# BlinkyBoard.net
KiCad netlist of a schematic drawn in EAGLE
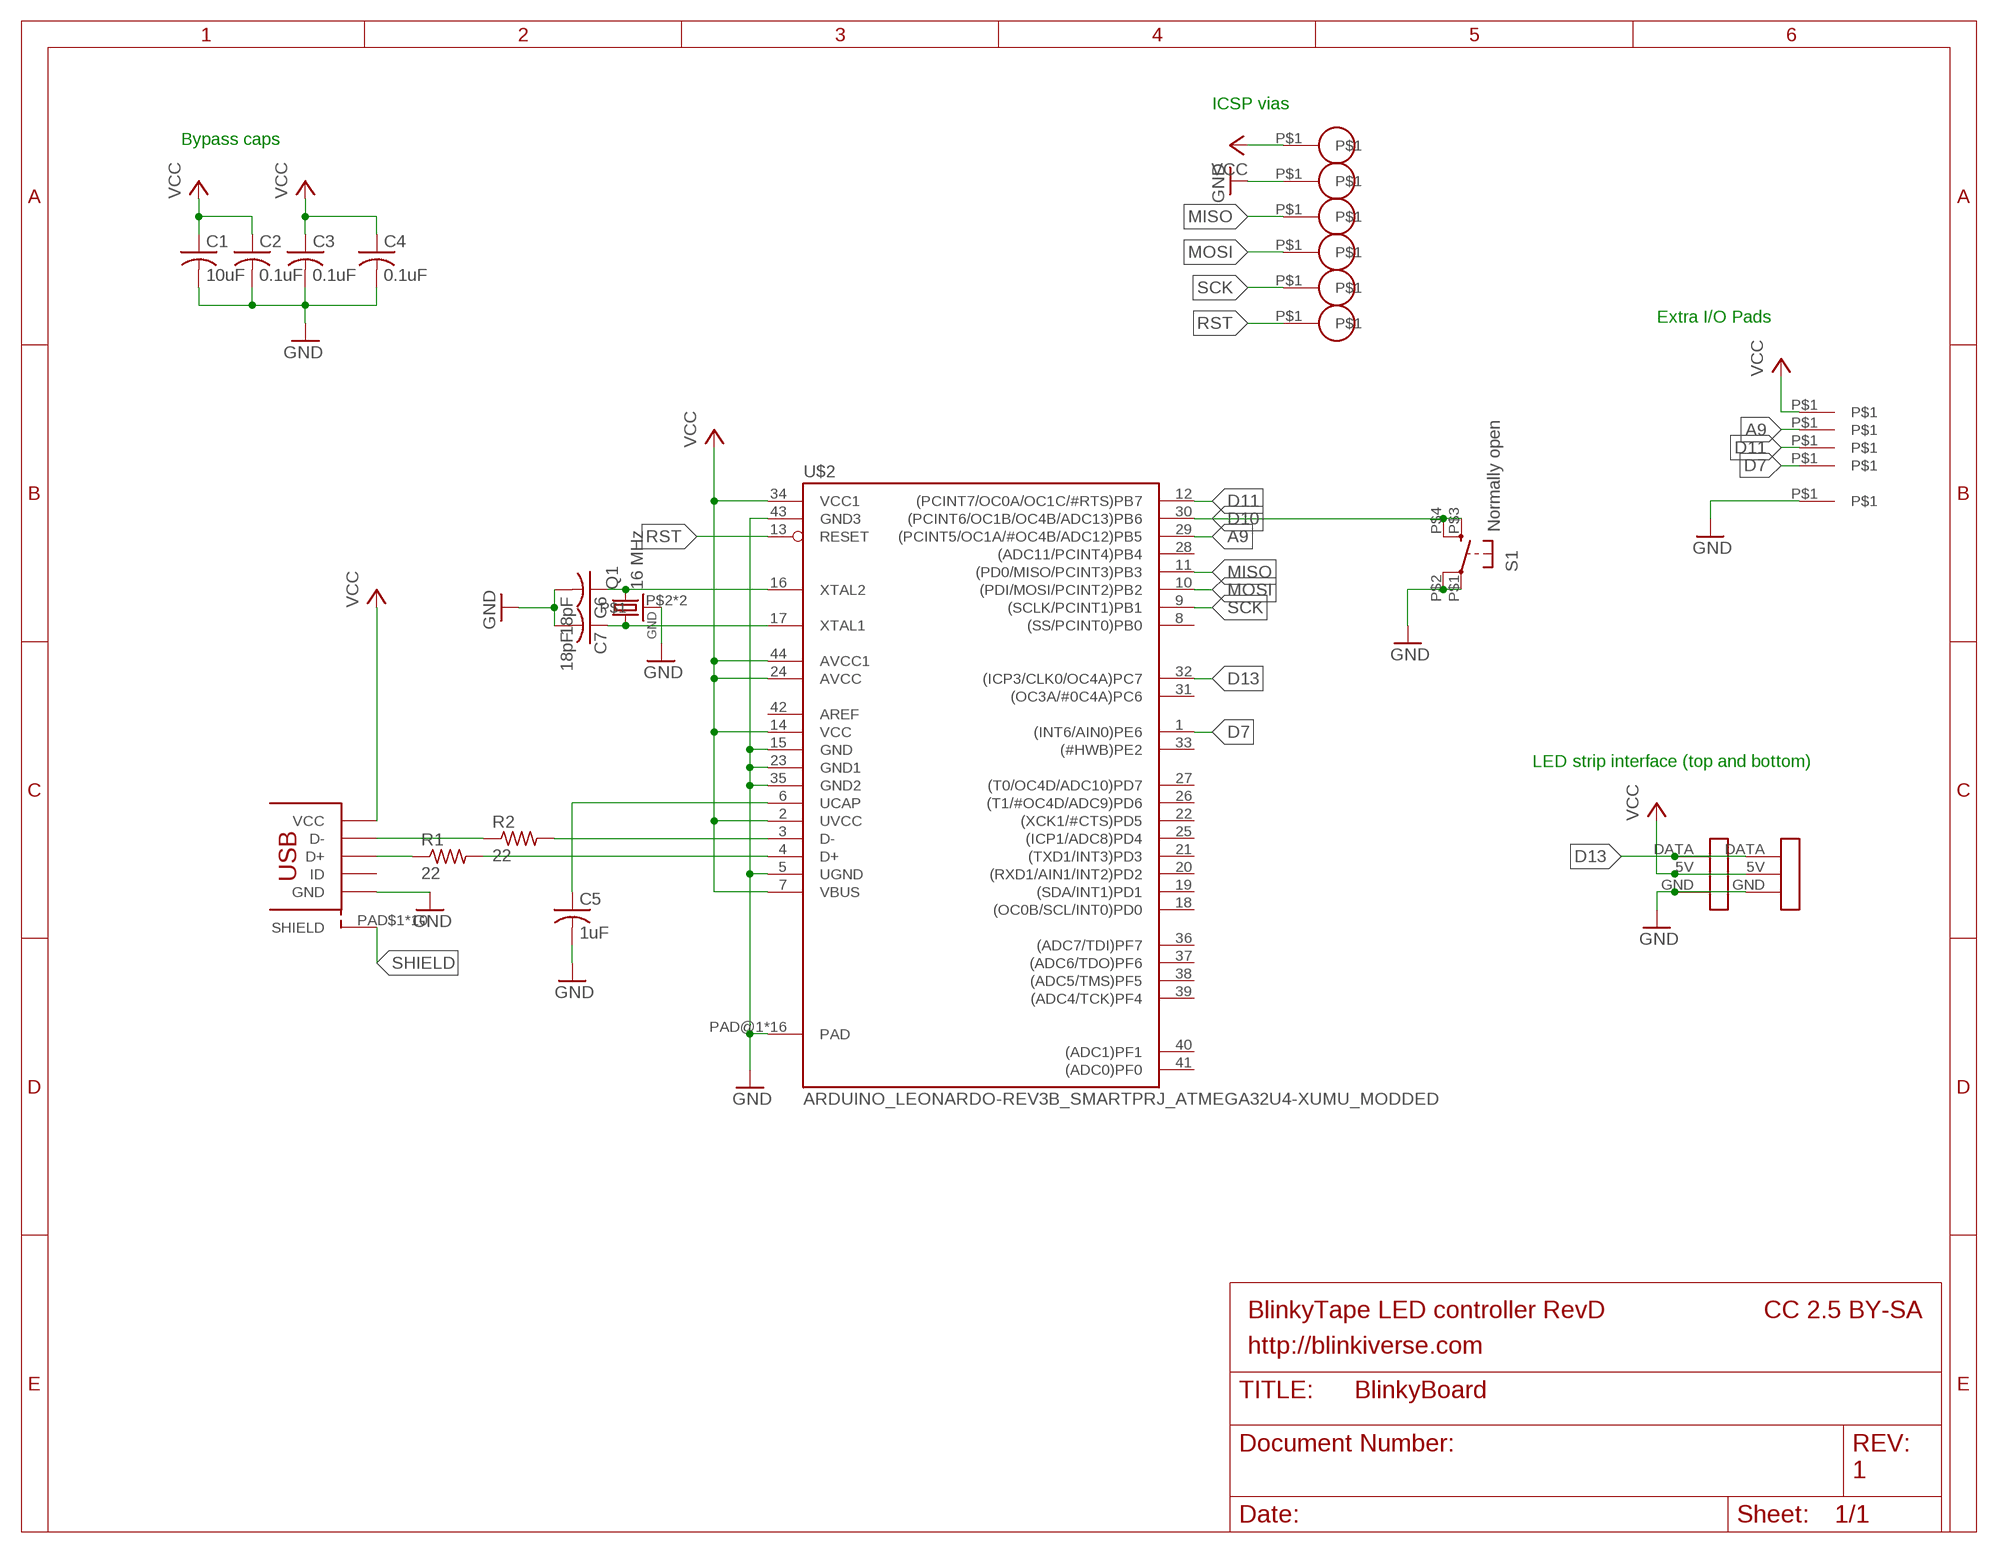
[diagram p0: schematic, sheet 1]

(export (version "E")
  (design (tool "Eeschema 10.0.6"))
  (components
    (comp (ref "C1")
      (value "10uF")
      (footprint "eagle-import:C0603K")
      (libsource (lib "eagle-import") (part "C-USC0603K"))
    )
    (comp (ref "C2")
      (value "0.1uF")
      (footprint "eagle-import:CAP_0402_KEMET_MEDIAN")
      (libsource (lib "eagle-import") (part "C_US"))
    )
    (comp (ref "C3")
      (value "0.1uF")
      (footprint "eagle-import:CAP_0402_KEMET_MEDIAN")
      (libsource (lib "eagle-import") (part "C_US"))
    )
    (comp (ref "C4")
      (value "0.1uF")
      (footprint "eagle-import:CAP_0402_KEMET_MEDIAN")
      (libsource (lib "eagle-import") (part "C_US"))
    )
    (comp (ref "C5")
      (value "1uF")
      (footprint "eagle-import:CAP_0402_KEMET_MEDIAN")
      (libsource (lib "eagle-import") (part "C_US"))
    )
    (comp (ref "C6")
      (value "18pF")
      (footprint "eagle-import:CAP_0402_KEMET_MEDIAN")
      (libsource (lib "eagle-import") (part "C_US"))
    )
    (comp (ref "C7")
      (value "18pF")
      (footprint "eagle-import:CAP_0402_KEMET_MEDIAN")
      (libsource (lib "eagle-import") (part "C_US"))
    )
    (comp (ref "Q1")
      (value "16 MHz")
      (footprint "eagle-import:CRSYTAL_2520")
      (libsource (lib "eagle-import") (part "CRYSTAL_4PAD2520"))
    )
    (comp (ref "R1")
      (value "22")
      (footprint "eagle-import:RES_0402_KEMET_MEDIAN")
      (libsource (lib "eagle-import") (part "R_US"))
    )
    (comp (ref "R2")
      (value "22")
      (footprint "eagle-import:RES_0402_KEMET_MEDIAN")
      (libsource (lib "eagle-import") (part "R_US"))
    )
    (comp (ref "S1")
      (value "Normally open")
      (footprint "eagle-import:GLOWBOARD_KMR211G_SWITCH")
      (libsource (lib "eagle-import") (part "GLOWBOARD_KMR211G"))
    )
    (comp (ref "U$1")
      (value "TEST_VIA")
      (footprint "eagle-import:TEST_VIA_.5MM")
      (libsource (lib "eagle-import") (part "TEST_VIA"))
    )
    (comp (ref "U$2")
      (value "ARDUINO_LEONARDO-REV3B_SMARTPRJ_ATMEGA32U4-XUMU_MODDED")
      (footprint "eagle-import:QFN44ML_7X7_LONGLEADS_MOD")
      (libsource (lib "eagle-import") (part "ARDUINO_LEONARDO-REV3B_SMARTPRJ_ATMEGA32U4-XUMU_MODDED"))
    )
    (comp (ref "U$3")
      (value "TEST_VIA")
      (footprint "eagle-import:TEST_VIA_.5MM")
      (libsource (lib "eagle-import") (part "TEST_VIA"))
    )
    (comp (ref "U$4")
      (value "MICRO_USBSMT+THRUHULE")
      (footprint "eagle-import:MICRO_USB_FCI_THRUHOLE")
      (libsource (lib "eagle-import") (part "MICRO_USBSMT+THRUHULE"))
    )
    (comp (ref "U$5")
      (value "TEST_VIA")
      (footprint "eagle-import:TEST_VIA_.5MM")
      (libsource (lib "eagle-import") (part "TEST_VIA"))
    )
    (comp (ref "U$6")
      (value "TEST_VIA")
      (footprint "eagle-import:TEST_VIA_.5MM")
      (libsource (lib "eagle-import") (part "TEST_VIA"))
    )
    (comp (ref "U$7")
      (value "TEST_VIA")
      (footprint "eagle-import:TEST_VIA_.5MM")
      (libsource (lib "eagle-import") (part "TEST_VIA"))
    )
    (comp (ref "U$8")
      (value "TEST_VIA")
      (footprint "eagle-import:TEST_VIA_.5MM")
      (libsource (lib "eagle-import") (part "TEST_VIA"))
    )
    (comp (ref "U$10")
      (value "TEST_PAD_SMT")
      (footprint "eagle-import:TEST_PAD_SMT")
      (libsource (lib "eagle-import") (part "TEST_PAD_SMT"))
    )
    (comp (ref "U$11")
      (value "TEST_PAD_SMT")
      (footprint "eagle-import:TEST_PAD_SMT")
      (libsource (lib "eagle-import") (part "TEST_PAD_SMT"))
    )
    (comp (ref "U$12")
      (value "TEST_PAD_SMT")
      (footprint "eagle-import:TEST_PAD_SMT")
      (libsource (lib "eagle-import") (part "TEST_PAD_SMT"))
    )
    (comp (ref "U$13")
      (value "TEST_PAD_SMT")
      (footprint "eagle-import:TEST_PAD_SMT")
      (libsource (lib "eagle-import") (part "TEST_PAD_SMT"))
    )
    (comp (ref "U$14")
      (value "TEST_PAD_SMT")
      (footprint "eagle-import:TEST_PAD_SMT")
      (libsource (lib "eagle-import") (part "TEST_PAD_SMT"))
    )
    (comp (ref "WS1")
      (value "WS2811_CONNECTORSTRIP")
      (footprint "eagle-import:WS2811_CONNECTOR")
      (libsource (lib "eagle-import") (part "WS2811_CONNECTORSTRIP"))
    )
    (comp (ref "WS3")
      (value "WS2811_CONNECTORSTRIP")
      (footprint "eagle-import:WS2811_CONNECTOR")
      (libsource (lib "eagle-import") (part "WS2811_CONNECTORSTRIP"))
    )
  )
  (nets
    (net (code "1") (name "/AREF") (class "Default")
      (node (ref "U$2") (pin "42") (pinfunction "AREF_42") (pintype "power_in"))
    )
    (net (code "2") (name "A9") (class "Default")
      (node (ref "U$11") (pin "P$1") (pinfunction "P$1_P$1") (pintype "bidirectional"))
      (node (ref "U$2") (pin "29") (pinfunction "(PCINT5/OC1A/#OC4B/ADC12)PB5_29") (pintype "bidirectional"))
    )
    (net (code "3") (name "D7") (class "Default")
      (node (ref "U$10") (pin "P$1") (pinfunction "P$1_P$1") (pintype "bidirectional"))
      (node (ref "U$2") (pin "1") (pinfunction "(INT6/AIN0)PE6_1") (pintype "bidirectional"))
    )
    (net (code "4") (name "D10") (class "Default")
      (node (ref "S1") (pin "P$3") (pinfunction "S_P$3") (pintype "passive"))
      (node (ref "S1") (pin "P$4") (pinfunction "S1_P$4") (pintype "passive"))
      (node (ref "U$2") (pin "30") (pinfunction "(PCINT6/OC1B/OC4B/ADC13)PB6_30") (pintype "bidirectional"))
    )
    (net (code "5") (name "D11") (class "Default")
      (node (ref "U$14") (pin "P$1") (pinfunction "P$1_P$1") (pintype "bidirectional"))
      (node (ref "U$2") (pin "12") (pinfunction "(PCINT7/OC0A/OC1C/#RTS)PB7_12") (pintype "bidirectional"))
    )
    (net (code "6") (name "D13") (class "Default")
      (node (ref "U$2") (pin "32") (pinfunction "(ICP3/CLK0/OC4A)PC7_32") (pintype "bidirectional"))
      (node (ref "WS1") (pin "DATA") (pinfunction "DATA_DATA") (pintype "bidirectional"))
      (node (ref "WS3") (pin "DATA") (pinfunction "DATA_DATA") (pintype "bidirectional"))
    )
    (net (code "7") (name "GND") (class "Default")
      (node (ref "C1") (pin "2") (pinfunction "2_2") (pintype "passive"))
      (node (ref "C2") (pin "P$2") (pinfunction "2_P$2") (pintype "passive"))
      (node (ref "C3") (pin "P$2") (pinfunction "2_P$2") (pintype "passive"))
      (node (ref "C4") (pin "P$2") (pinfunction "2_P$2") (pintype "passive"))
      (node (ref "C5") (pin "P$2") (pinfunction "2_P$2") (pintype "passive"))
      (node (ref "C6") (pin "P$2") (pinfunction "2_P$2") (pintype "passive"))
      (node (ref "C7") (pin "P$2") (pinfunction "2_P$2") (pintype "passive"))
      (node (ref "Q1") (pin "P$2") (pinfunction "P$1_P$2") (pintype "bidirectional"))
      (node (ref "Q1") (pin "P$4") (pinfunction "P$1_P$4") (pintype "bidirectional"))
      (node (ref "S1") (pin "P$1") (pinfunction "P_P$1") (pintype "passive"))
      (node (ref "S1") (pin "P$2") (pinfunction "P1_P$2") (pintype "passive"))
      (node (ref "U$13") (pin "P$1") (pinfunction "P$1_P$1") (pintype "bidirectional"))
      (node (ref "U$2") (pin "15") (pinfunction "GND_15") (pintype "power_in"))
      (node (ref "U$2") (pin "23") (pinfunction "GND1_23") (pintype "power_in"))
      (node (ref "U$2") (pin "35") (pinfunction "GND2_35") (pintype "power_in"))
      (node (ref "U$2") (pin "43") (pinfunction "GND3_43") (pintype "power_in"))
      (node (ref "U$2") (pin "5") (pinfunction "UGND_5") (pintype "power_in"))
      (node (ref "U$2") (pin "PAD@1") (pinfunction "PAD_PAD@1") (pintype "power_in"))
      (node (ref "U$2") (pin "PAD@10") (pinfunction "PAD_PAD@10") (pintype "power_in"))
      (node (ref "U$2") (pin "PAD@11") (pinfunction "PAD_PAD@11") (pintype "power_in"))
      (node (ref "U$2") (pin "PAD@12") (pinfunction "PAD_PAD@12") (pintype "power_in"))
      (node (ref "U$2") (pin "PAD@13") (pinfunction "PAD_PAD@13") (pintype "power_in"))
      (node (ref "U$2") (pin "PAD@14") (pinfunction "PAD_PAD@14") (pintype "power_in"))
      (node (ref "U$2") (pin "PAD@15") (pinfunction "PAD_PAD@15") (pintype "power_in"))
      (node (ref "U$2") (pin "PAD@16") (pinfunction "PAD_PAD@16") (pintype "power_in"))
      (node (ref "U$2") (pin "PAD@2") (pinfunction "PAD_PAD@2") (pintype "power_in"))
      (node (ref "U$2") (pin "PAD@3") (pinfunction "PAD_PAD@3") (pintype "power_in"))
      (node (ref "U$2") (pin "PAD@4") (pinfunction "PAD_PAD@4") (pintype "power_in"))
      (node (ref "U$2") (pin "PAD@5") (pinfunction "PAD_PAD@5") (pintype "power_in"))
      (node (ref "U$2") (pin "PAD@6") (pinfunction "PAD_PAD@6") (pintype "power_in"))
      (node (ref "U$2") (pin "PAD@7") (pinfunction "PAD_PAD@7") (pintype "power_in"))
      (node (ref "U$2") (pin "PAD@8") (pinfunction "PAD_PAD@8") (pintype "power_in"))
      (node (ref "U$2") (pin "PAD@9") (pinfunction "PAD_PAD@9") (pintype "power_in"))
      (node (ref "U$4") (pin "PIN$5") (pinfunction "GND_PIN$5") (pintype "bidirectional"))
      (node (ref "U$7") (pin "P$1") (pinfunction "P$1_P$1") (pintype "bidirectional"))
      (node (ref "WS1") (pin "GND") (pinfunction "GND_GND") (pintype "bidirectional"))
      (node (ref "WS3") (pin "GND") (pinfunction "GND_GND") (pintype "bidirectional"))
    )
    (net (code "8") (name "MISO") (class "Default")
      (node (ref "U$1") (pin "P$1") (pinfunction "P$1_P$1") (pintype "bidirectional"))
      (node (ref "U$2") (pin "11") (pinfunction "(PD0/MISO/PCINT3)PB3_11") (pintype "bidirectional"))
    )
    (net (code "9") (name "MOSI") (class "Default")
      (node (ref "U$2") (pin "10") (pinfunction "(PDI/MOSI/PCINT2)PB2_10") (pintype "bidirectional"))
      (node (ref "U$3") (pin "P$1") (pinfunction "P$1_P$1") (pintype "bidirectional"))
    )
    (net (code "10") (name "Net-(C5-1)") (class "Default")
      (node (ref "C5") (pin "P$1") (pinfunction "1_P$1") (pintype "passive"))
      (node (ref "U$2") (pin "6") (pinfunction "UCAP_6") (pintype "passive"))
    )
    (net (code "11") (name "Net-(C6-1)") (class "Default")
      (node (ref "C6") (pin "P$1") (pinfunction "1_P$1") (pintype "passive"))
      (node (ref "Q1") (pin "P$3") (pinfunction "2_P$3") (pintype "passive"))
      (node (ref "U$2") (pin "16") (pinfunction "XTAL2_16") (pintype "bidirectional"))
    )
    (net (code "12") (name "Net-(C7-1)") (class "Default")
      (node (ref "C7") (pin "P$1") (pinfunction "1_P$1") (pintype "passive"))
      (node (ref "Q1") (pin "P$1") (pinfunction "1_P$1") (pintype "passive"))
      (node (ref "U$2") (pin "17") (pinfunction "XTAL1_17") (pintype "bidirectional"))
    )
    (net (code "13") (name "Net-(R1-1)") (class "Default")
      (node (ref "R1") (pin "P$1") (pinfunction "1_P$1") (pintype "passive"))
      (node (ref "U$4") (pin "PIN$3") (pinfunction "D+_PIN$3") (pintype "bidirectional"))
    )
    (net (code "14") (name "Net-(R1-2)") (class "Default")
      (node (ref "R1") (pin "P$2") (pinfunction "2_P$2") (pintype "passive"))
      (node (ref "U$2") (pin "4") (pinfunction "D+_4") (pintype "bidirectional"))
    )
    (net (code "15") (name "Net-(R2-1)") (class "Default")
      (node (ref "R2") (pin "P$1") (pinfunction "1_P$1") (pintype "passive"))
      (node (ref "U$4") (pin "PIN$2") (pinfunction "D-_PIN$2") (pintype "bidirectional"))
    )
    (net (code "16") (name "Net-(R2-2)") (class "Default")
      (node (ref "R2") (pin "P$2") (pinfunction "2_P$2") (pintype "passive"))
      (node (ref "U$2") (pin "3") (pinfunction "D-_3") (pintype "bidirectional"))
    )
    (net (code "17") (name "RST") (class "Default")
      (node (ref "U$2") (pin "13") (pinfunction "RESET_13") (pintype "input"))
      (node (ref "U$6") (pin "P$1") (pinfunction "P$1_P$1") (pintype "bidirectional"))
    )
    (net (code "18") (name "SCK") (class "Default")
      (node (ref "U$2") (pin "9") (pinfunction "(SCLK/PCINT1)PB1_9") (pintype "bidirectional"))
      (node (ref "U$5") (pin "P$1") (pinfunction "P$1_P$1") (pintype "bidirectional"))
    )
    (net (code "19") (name "SHIELD") (class "Default")
      (node (ref "U$4") (pin "PAD$1") (pinfunction "SHIELD_PAD$1") (pintype "bidirectional"))
      (node (ref "U$4") (pin "PAD$10") (pinfunction "SHIELD_PAD$10") (pintype "bidirectional"))
      (node (ref "U$4") (pin "PAD$2") (pinfunction "SHIELD_PAD$2") (pintype "bidirectional"))
      (node (ref "U$4") (pin "PAD$3") (pinfunction "SHIELD_PAD$3") (pintype "bidirectional"))
      (node (ref "U$4") (pin "PAD$4") (pinfunction "SHIELD_PAD$4") (pintype "bidirectional"))
      (node (ref "U$4") (pin "PAD$5") (pinfunction "SHIELD_PAD$5") (pintype "bidirectional"))
      (node (ref "U$4") (pin "PAD$6") (pinfunction "SHIELD_PAD$6") (pintype "bidirectional"))
      (node (ref "U$4") (pin "PAD$7") (pinfunction "SHIELD_PAD$7") (pintype "bidirectional"))
      (node (ref "U$4") (pin "PAD$8") (pinfunction "SHIELD_PAD$8") (pintype "bidirectional"))
      (node (ref "U$4") (pin "PAD$9") (pinfunction "SHIELD_PAD$9") (pintype "bidirectional"))
    )
    (net (code "20") (name "VCC") (class "Default")
      (node (ref "C1") (pin "1") (pinfunction "1_1") (pintype "passive"))
      (node (ref "C2") (pin "P$1") (pinfunction "1_P$1") (pintype "passive"))
      (node (ref "C3") (pin "P$1") (pinfunction "1_P$1") (pintype "passive"))
      (node (ref "C4") (pin "P$1") (pinfunction "1_P$1") (pintype "passive"))
      (node (ref "U$12") (pin "P$1") (pinfunction "P$1_P$1") (pintype "bidirectional"))
      (node (ref "U$2") (pin "14") (pinfunction "VCC_14") (pintype "power_in"))
      (node (ref "U$2") (pin "2") (pinfunction "UVCC_2") (pintype "power_in"))
      (node (ref "U$2") (pin "24") (pinfunction "AVCC_24") (pintype "power_in"))
      (node (ref "U$2") (pin "34") (pinfunction "VCC1_34") (pintype "power_in"))
      (node (ref "U$2") (pin "44") (pinfunction "AVCC1_44") (pintype "power_in"))
      (node (ref "U$2") (pin "7") (pinfunction "VBUS_7") (pintype "input"))
      (node (ref "U$4") (pin "PIN$1") (pinfunction "VCC_PIN$1") (pintype "bidirectional"))
      (node (ref "U$8") (pin "P$1") (pinfunction "P$1_P$1") (pintype "bidirectional"))
      (node (ref "WS1") (pin "5V") (pinfunction "5V_5V") (pintype "bidirectional"))
      (node (ref "WS3") (pin "5V") (pinfunction "5V_5V") (pintype "bidirectional"))
    )
    (net (code "21") (name "unconnected-(U$2-(#HWB)PE2-Pad33)") (class "Default")
      (node (ref "U$2") (pin "33") (pinfunction "(#HWB)PE2_33") (pintype "bidirectional"))
    )
    (net (code "22") (name "unconnected-(U$2-(ADC0)PF0-Pad41)") (class "Default")
      (node (ref "U$2") (pin "41") (pinfunction "(ADC0)PF0_41") (pintype "bidirectional"))
    )
    (net (code "23") (name "unconnected-(U$2-(ADC1)PF1-Pad40)") (class "Default")
      (node (ref "U$2") (pin "40") (pinfunction "(ADC1)PF1_40") (pintype "bidirectional"))
    )
    (net (code "24") (name "unconnected-(U$2-(ADC4{slash}TCK)PF4-Pad39)") (class "Default")
      (node (ref "U$2") (pin "39") (pinfunction "(ADC4/TCK)PF4_39") (pintype "bidirectional"))
    )
    (net (code "25") (name "unconnected-(U$2-(ADC5{slash}TMS)PF5-Pad38)") (class "Default")
      (node (ref "U$2") (pin "38") (pinfunction "(ADC5/TMS)PF5_38") (pintype "bidirectional"))
    )
    (net (code "26") (name "unconnected-(U$2-(ADC6{slash}TDO)PF6-Pad37)") (class "Default")
      (node (ref "U$2") (pin "37") (pinfunction "(ADC6/TDO)PF6_37") (pintype "bidirectional"))
    )
    (net (code "27") (name "unconnected-(U$2-(ADC7{slash}TDI)PF7-Pad36)") (class "Default")
      (node (ref "U$2") (pin "36") (pinfunction "(ADC7/TDI)PF7_36") (pintype "bidirectional"))
    )
    (net (code "28") (name "unconnected-(U$2-(ADC11{slash}PCINT4)PB4-Pad28)") (class "Default")
      (node (ref "U$2") (pin "28") (pinfunction "(ADC11/PCINT4)PB4_28") (pintype "bidirectional"))
    )
    (net (code "29") (name "unconnected-(U$2-(ICP1{slash}ADC8)PD4-Pad25)") (class "Default")
      (node (ref "U$2") (pin "25") (pinfunction "(ICP1/ADC8)PD4_25") (pintype "bidirectional"))
    )
    (net (code "30") (name "unconnected-(U$2-(OC0B{slash}SCL{slash}INT0)PD0-Pad18)") (class "Default")
      (node (ref "U$2") (pin "18") (pinfunction "(OC0B/SCL/INT0)PD0_18") (pintype "bidirectional"))
    )
    (net (code "31") (name "unconnected-(U$2-(OC3A{slash}#0C4A)PC6-Pad31)") (class "Default")
      (node (ref "U$2") (pin "31") (pinfunction "(OC3A/#0C4A)PC6_31") (pintype "bidirectional"))
    )
    (net (code "32") (name "unconnected-(U$2-(RXD1{slash}AIN1{slash}INT2)PD2-Pad20)") (class "Default")
      (node (ref "U$2") (pin "20") (pinfunction "(RXD1/AIN1/INT2)PD2_20") (pintype "bidirectional"))
    )
    (net (code "33") (name "unconnected-(U$2-(SDA{slash}INT1)PD1-Pad19)") (class "Default")
      (node (ref "U$2") (pin "19") (pinfunction "(SDA/INT1)PD1_19") (pintype "bidirectional"))
    )
    (net (code "34") (name "unconnected-(U$2-(SS{slash}PCINT0)PB0-Pad8)") (class "Default")
      (node (ref "U$2") (pin "8") (pinfunction "(SS/PCINT0)PB0_8") (pintype "bidirectional"))
    )
    (net (code "35") (name "unconnected-(U$2-(T0{slash}OC4D{slash}ADC10)PD7-Pad27)") (class "Default")
      (node (ref "U$2") (pin "27") (pinfunction "(T0/OC4D/ADC10)PD7_27") (pintype "bidirectional"))
    )
    (net (code "36") (name "unconnected-(U$2-(T1{slash}#OC4D{slash}ADC9)PD6-Pad26)") (class "Default")
      (node (ref "U$2") (pin "26") (pinfunction "(T1/#OC4D/ADC9)PD6_26") (pintype "bidirectional"))
    )
    (net (code "37") (name "unconnected-(U$2-(TXD1{slash}INT3)PD3-Pad21)") (class "Default")
      (node (ref "U$2") (pin "21") (pinfunction "(TXD1/INT3)PD3_21") (pintype "bidirectional"))
    )
    (net (code "38") (name "unconnected-(U$2-(XCK1{slash}#CTS)PD5-Pad22)") (class "Default")
      (node (ref "U$2") (pin "22") (pinfunction "(XCK1/#CTS)PD5_22") (pintype "bidirectional"))
    )
    (net (code "39") (name "unconnected-(U$4-ID-PadPIN$4)") (class "Default")
      (node (ref "U$4") (pin "PIN$4") (pinfunction "ID_PIN$4") (pintype "bidirectional"))
    )
  )
)
